# voltmeter-hack.net
KiCad netlist of a schematic drawn in EAGLE
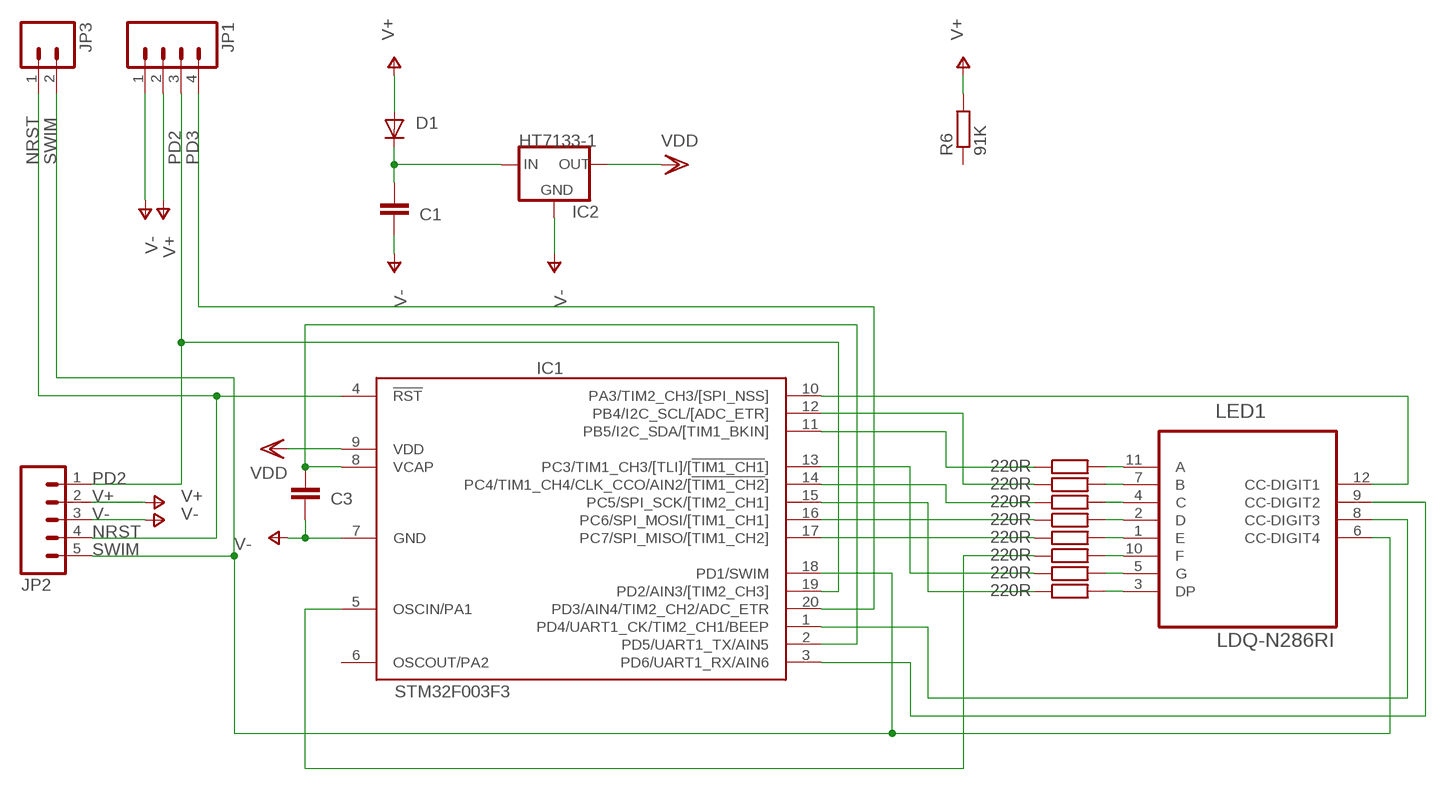
[diagram p0: schematic, sheet 1]

(export (version "E")
  (design (tool "Eeschema 10.0.6"))
  (components
    (comp (ref "C1")
      (value "C-EUC0603")
      (footprint "eagle-import:C0603")
      (libsource (lib "eagle-import") (part "C-EUC0603"))
    )
    (comp (ref "C3")
      (value "C-EUC0603")
      (footprint "eagle-import:C0603")
      (libsource (lib "eagle-import") (part "C-EUC0603"))
    )
    (comp (ref "D1")
      (value "DIODE-SOD-123")
      (footprint "eagle-import:SOD-123")
      (libsource (lib "eagle-import") (part "DIODE-SOD-123"))
    )
    (comp (ref "IC1")
      (value "STM32F003F3")
      (footprint "eagle-import:TSSOP20")
      (libsource (lib "eagle-import") (part "STM32F003F3"))
    )
    (comp (ref "IC2")
      (value "HT7133-1")
      (footprint "eagle-import:SOT89R")
      (libsource (lib "eagle-import") (part "XC63FPP"))
    )
    (comp (ref "JP1")
      (value "M04PTH")
      (footprint "eagle-import:1X04")
      (libsource (lib "eagle-import") (part "M04PTH"))
    )
    (comp (ref "JP2")
      (value "M05PTH")
      (footprint "eagle-import:1X05")
      (libsource (lib "eagle-import") (part "M05PTH"))
    )
    (comp (ref "JP3")
      (value "M02PTH")
      (footprint "eagle-import:1X02")
      (libsource (lib "eagle-import") (part "M02PTH"))
    )
    (comp (ref "LED1")
      (value "LDQ-N286RI")
      (footprint "eagle-import:LUMEX_LDQ-N286RI")
      (libsource (lib "eagle-import") (part "LDQ-N286RI"))
    )
    (comp (ref "R1")
      (value "220R")
      (footprint "eagle-import:R0603")
      (libsource (lib "eagle-import") (part "R-EU_R0603"))
    )
    (comp (ref "R2")
      (value "220R")
      (footprint "eagle-import:R0603")
      (libsource (lib "eagle-import") (part "R-EU_R0603"))
    )
    (comp (ref "R4")
      (value "220R")
      (footprint "eagle-import:R0603")
      (libsource (lib "eagle-import") (part "R-EU_R0603"))
    )
    (comp (ref "R5")
      (value "220R")
      (footprint "eagle-import:R0603")
      (libsource (lib "eagle-import") (part "R-EU_R0603"))
    )
    (comp (ref "R6")
      (value "91K")
      (footprint "eagle-import:R0603")
      (libsource (lib "eagle-import") (part "R-EU_R0603"))
    )
    (comp (ref "R7")
      (value "220R")
      (footprint "eagle-import:R0603")
      (libsource (lib "eagle-import") (part "R-EU_R0603"))
    )
    (comp (ref "R8")
      (value "220R")
      (footprint "eagle-import:R0603")
      (libsource (lib "eagle-import") (part "R-EU_R0603"))
    )
    (comp (ref "R13")
      (value "220R")
      (footprint "eagle-import:R0603")
      (libsource (lib "eagle-import") (part "R-EU_R0603"))
    )
    (comp (ref "R16")
      (value "220R")
      (footprint "eagle-import:R0603")
      (libsource (lib "eagle-import") (part "R-EU_R0603"))
    )
  )
  (nets
    (net (code "1") (name "/NRST") (class "Default")
      (node (ref "IC1") (pin "4") (pinfunction "~{RST}_4") (pintype "input"))
      (node (ref "JP2") (pin "4") (pinfunction "4_4") (pintype "passive"))
      (node (ref "JP3") (pin "1") (pinfunction "1_1") (pintype "passive"))
    )
    (net (code "2") (name "/PD2") (class "Default")
      (node (ref "IC1") (pin "19") (pinfunction "PD2/AIN3/[TIM2_CH3]_19") (pintype "bidirectional"))
      (node (ref "JP1") (pin "3") (pinfunction "3_3") (pintype "passive"))
      (node (ref "JP2") (pin "1") (pinfunction "1_1") (pintype "passive"))
    )
    (net (code "3") (name "/PD3") (class "Default")
      (node (ref "IC1") (pin "20") (pinfunction "PD3/AIN4/TIM2_CH2/ADC_ETR_20") (pintype "bidirectional"))
      (node (ref "JP1") (pin "4") (pinfunction "4_4") (pintype "passive"))
    )
    (net (code "4") (name "/SWIM") (class "Default")
      (node (ref "IC1") (pin "18") (pinfunction "PD1/SWIM_18") (pintype "bidirectional"))
      (node (ref "JP2") (pin "5") (pinfunction "5_5") (pintype "passive"))
      (node (ref "JP3") (pin "2") (pinfunction "2_2") (pintype "passive"))
      (node (ref "LED1") (pin "6") (pinfunction "CC-DIGIT4_6") (pintype "passive"))
    )
    (net (code "5") (name "Net-(IC1-OSCIN{slash}PA1)") (class "Default")
      (node (ref "IC1") (pin "5") (pinfunction "OSCIN/PA1_5") (pintype "bidirectional"))
      (node (ref "R16") (pin "1") (pinfunction "1_1") (pintype "passive"))
    )
    (net (code "6") (name "Net-(IC1-PA3{slash}TIM2_CH3{slash}[SPI_NSS])") (class "Default")
      (node (ref "IC1") (pin "10") (pinfunction "PA3/TIM2_CH3/[SPI_NSS]_10") (pintype "bidirectional"))
      (node (ref "LED1") (pin "12") (pinfunction "CC-DIGIT1_12") (pintype "passive"))
    )
    (net (code "7") (name "Net-(IC1-PB4{slash}I2C_SCL{slash}[ADC_ETR])") (class "Default")
      (node (ref "IC1") (pin "12") (pinfunction "PB4/I2C_SCL/[ADC_ETR]_12") (pintype "bidirectional"))
      (node (ref "R2") (pin "1") (pinfunction "1_1") (pintype "passive"))
    )
    (net (code "8") (name "Net-(IC1-PB5{slash}I2C_SDA{slash}[TIM1_BKIN])") (class "Default")
      (node (ref "IC1") (pin "11") (pinfunction "PB5/I2C_SDA/[TIM1_BKIN]_11") (pintype "bidirectional"))
      (node (ref "R1") (pin "1") (pinfunction "1_1") (pintype "passive"))
    )
    (net (code "9") (name "Net-(IC1-PC3{slash}TIM1_CH3{slash}[TLI]{slash}[~{TIM1_CH1}])") (class "Default")
      (node (ref "IC1") (pin "13") (pinfunction "PC3/TIM1_CH3/[TLI]/[~{TIM1_CH1}]_13") (pintype "bidirectional"))
      (node (ref "R7") (pin "1") (pinfunction "1_1") (pintype "passive"))
    )
    (net (code "10") (name "Net-(IC1-PC4{slash}TIM1_CH4{slash}CLK_CCO{slash}AIN2{slash}[~{TIM1_CH2}])") (class "Default")
      (node (ref "IC1") (pin "14") (pinfunction "PC4/TIM1_CH4/CLK_CCO/AIN2/[~{TIM1_CH2}]_14") (pintype "bidirectional"))
      (node (ref "R13") (pin "1") (pinfunction "1_1") (pintype "passive"))
    )
    (net (code "11") (name "Net-(IC1-PC5{slash}SPI_SCK{slash}[TIM2_CH1])") (class "Default")
      (node (ref "IC1") (pin "15") (pinfunction "PC5/SPI_SCK/[TIM2_CH1]_15") (pintype "bidirectional"))
      (node (ref "R8") (pin "1") (pinfunction "1_1") (pintype "passive"))
    )
    (net (code "12") (name "Net-(IC1-PC6{slash}SPI_MOSI{slash}[TIM1_CH1])") (class "Default")
      (node (ref "IC1") (pin "16") (pinfunction "PC6/SPI_MOSI/[TIM1_CH1]_16") (pintype "bidirectional"))
      (node (ref "R4") (pin "1") (pinfunction "1_1") (pintype "passive"))
    )
    (net (code "13") (name "Net-(IC1-PC7{slash}SPI_MISO{slash}[TIM1_CH2])") (class "Default")
      (node (ref "IC1") (pin "17") (pinfunction "PC7/SPI_MISO/[TIM1_CH2]_17") (pintype "bidirectional"))
      (node (ref "R5") (pin "1") (pinfunction "1_1") (pintype "passive"))
    )
    (net (code "14") (name "Net-(IC1-PD4{slash}UART1_CK{slash}TIM2_CH1{slash}BEEP)") (class "Default")
      (node (ref "IC1") (pin "1") (pinfunction "PD4/UART1_CK/TIM2_CH1/BEEP_1") (pintype "bidirectional"))
      (node (ref "LED1") (pin "8") (pinfunction "CC-DIGIT3_8") (pintype "passive"))
    )
    (net (code "15") (name "Net-(IC1-PD5{slash}UART1_TX{slash}AIN5)") (class "Default")
      (node (ref "C3") (pin "2") (pinfunction "2_2") (pintype "passive"))
      (node (ref "IC1") (pin "2") (pinfunction "PD5/UART1_TX/AIN5_2") (pintype "bidirectional"))
      (node (ref "IC1") (pin "8") (pinfunction "VCAP_8") (pintype "power_in"))
    )
    (net (code "16") (name "Net-(IC1-PD6{slash}UART1_RX{slash}AIN6)") (class "Default")
      (node (ref "IC1") (pin "3") (pinfunction "PD6/UART1_RX/AIN6_3") (pintype "bidirectional"))
      (node (ref "LED1") (pin "9") (pinfunction "CC-DIGIT2_9") (pintype "passive"))
    )
    (net (code "17") (name "Net-(IC2-IN)") (class "Default")
      (node (ref "C1") (pin "2") (pinfunction "2_2") (pintype "passive"))
      (node (ref "D1") (pin "C") (pinfunction "C_C") (pintype "passive"))
      (node (ref "IC2") (pin "2") (pinfunction "IN_2") (pintype "input"))
    )
    (net (code "18") (name "Net-(LED1-A)") (class "Default")
      (node (ref "LED1") (pin "11") (pinfunction "A_11") (pintype "passive"))
      (node (ref "R1") (pin "2") (pinfunction "2_2") (pintype "passive"))
    )
    (net (code "19") (name "Net-(LED1-B)") (class "Default")
      (node (ref "LED1") (pin "7") (pinfunction "B_7") (pintype "passive"))
      (node (ref "R2") (pin "2") (pinfunction "2_2") (pintype "passive"))
    )
    (net (code "20") (name "Net-(LED1-C)") (class "Default")
      (node (ref "LED1") (pin "4") (pinfunction "C_4") (pintype "passive"))
      (node (ref "R13") (pin "2") (pinfunction "2_2") (pintype "passive"))
    )
    (net (code "21") (name "Net-(LED1-D)") (class "Default")
      (node (ref "LED1") (pin "2") (pinfunction "D_2") (pintype "passive"))
      (node (ref "R4") (pin "2") (pinfunction "2_2") (pintype "passive"))
    )
    (net (code "22") (name "Net-(LED1-DP)") (class "Default")
      (node (ref "LED1") (pin "3") (pinfunction "DP_3") (pintype "passive"))
      (node (ref "R8") (pin "2") (pinfunction "2_2") (pintype "passive"))
    )
    (net (code "23") (name "Net-(LED1-E)") (class "Default")
      (node (ref "LED1") (pin "1") (pinfunction "E_1") (pintype "passive"))
      (node (ref "R5") (pin "2") (pinfunction "2_2") (pintype "passive"))
    )
    (net (code "24") (name "Net-(LED1-F)") (class "Default")
      (node (ref "LED1") (pin "10") (pinfunction "F_10") (pintype "passive"))
      (node (ref "R16") (pin "2") (pinfunction "2_2") (pintype "passive"))
    )
    (net (code "25") (name "Net-(LED1-G)") (class "Default")
      (node (ref "LED1") (pin "5") (pinfunction "G_5") (pintype "passive"))
      (node (ref "R7") (pin "2") (pinfunction "2_2") (pintype "passive"))
    )
    (net (code "26") (name "V+") (class "Default")
      (node (ref "D1") (pin "A") (pinfunction "A_A") (pintype "passive"))
      (node (ref "JP1") (pin "2") (pinfunction "2_2") (pintype "passive"))
      (node (ref "JP2") (pin "2") (pinfunction "2_2") (pintype "passive"))
      (node (ref "R6") (pin "2") (pinfunction "2_2") (pintype "passive"))
    )
    (net (code "27") (name "V-") (class "Default")
      (node (ref "C1") (pin "1") (pinfunction "1_1") (pintype "passive"))
      (node (ref "C3") (pin "1") (pinfunction "1_1") (pintype "passive"))
      (node (ref "IC1") (pin "7") (pinfunction "GND_7") (pintype "power_in"))
      (node (ref "IC2") (pin "1") (pinfunction "GND_1") (pintype "input"))
      (node (ref "JP1") (pin "1") (pinfunction "1_1") (pintype "passive"))
      (node (ref "JP2") (pin "3") (pinfunction "3_3") (pintype "passive"))
    )
    (net (code "28") (name "VDD") (class "Default")
      (node (ref "IC1") (pin "9") (pinfunction "VDD_9") (pintype "power_in"))
      (node (ref "IC2") (pin "3") (pinfunction "OUT_3") (pintype "passive"))
    )
    (net (code "29") (name "unconnected-(IC1-OSCOUT{slash}PA2-Pad6)") (class "Default")
      (node (ref "IC1") (pin "6") (pinfunction "OSCOUT/PA2_6") (pintype "bidirectional"))
    )
    (net (code "30") (name "unconnected-(R6-Pad1)") (class "Default")
      (node (ref "R6") (pin "1") (pinfunction "1_1") (pintype "passive"))
    )
  )
)
